# EN-C200_RA0_USB.net
KiCad netlist of a schematic drawn in Altium Designer
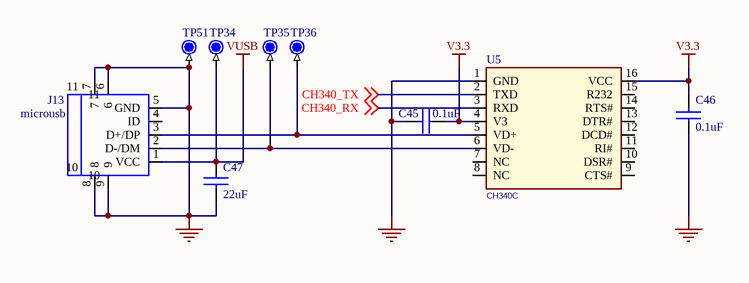
[diagram p0: EN-C200_RA0_USB.SchDoc]

(export (version "E")
  (design (tool "Eeschema 10.0.6"))
  (components
    (comp (ref "C45") (value "0.1uF") (footprint "SC0603") (libsource (lib "EN-C200_RA0") (part "CAP NP")))
    (comp (ref "C46") (value "0.1uF") (footprint "SC0603") (libsource (lib "EN-C200_RA0") (part "CAP NP")))
    (comp (ref "C47") (value "22uF") (footprint "SC0805") (libsource (lib "EN-C200_RA0") (part "CAP NP")))
    (comp (ref "J13")
      (value "microusb")
      (footprint "MICROUSB_D")
      (libsource (lib "EN-C200_RA0") (part "microusb"))
    )
    (comp (ref "TP34") (value "NC") (footprint "TP32-SMD") (libsource (lib "EN-C200_RA0") (part "TP")))
    (comp (ref "TP35") (value "NC") (footprint "TP32-SMD") (libsource (lib "EN-C200_RA0") (part "TP")))
    (comp (ref "TP36") (value "NC") (footprint "TP32-SMD") (libsource (lib "EN-C200_RA0") (part "TP")))
    (comp (ref "TP51") (value "NC") (footprint "TP32-SMD") (libsource (lib "EN-C200_RA0") (part "TP")))
    (comp (ref "U5")
      (value "CH340C")
      (footprint "SOP16-50-150A")
      (libsource (lib "EN-C200_RA0") (part "CH340C_0"))
    )
  )
  (nets
    (net (code "1") (name "CH340_RX") (class "Default")
      (node (ref "U5") (pin "3") (pinfunction "RXD_3") (pintype "passive"))
    )
    (net (code "2") (name "CH340_TX") (class "Default")
      (node (ref "U5") (pin "2") (pinfunction "TXD_2") (pintype "passive"))
    )
    (net (code "3") (name "GND") (class "Default")
      (node (ref "C45") (pin "2") (pinfunction "2_2") (pintype "passive"))
      (node (ref "C46") (pin "1") (pinfunction "1_1") (pintype "passive"))
      (node (ref "C47") (pin "2") (pinfunction "2_2") (pintype "passive"))
      (node (ref "J13") (pin "5") (pinfunction "GND_5") (pintype "passive"))
      (node (ref "J13") (pin "6") (pinfunction "6_6") (pintype "passive"))
      (node (ref "J13") (pin "7") (pinfunction "7_7") (pintype "passive"))
      (node (ref "J13") (pin "8") (pinfunction "8_8") (pintype "passive"))
      (node (ref "J13") (pin "9") (pinfunction "9_9") (pintype "passive"))
      (node (ref "TP51") (pin "1") (pinfunction "1_1") (pintype "input"))
      (node (ref "U5") (pin "1") (pinfunction "GND_1") (pintype "power_in"))
    )
    (net (code "4") (name "Net-(J13-D+{slash}DP)") (class "Default")
      (node (ref "J13") (pin "3") (pinfunction "D+/DP_3") (pintype "passive"))
      (node (ref "TP36") (pin "1") (pinfunction "1_1") (pintype "input"))
      (node (ref "U5") (pin "5") (pinfunction "VD+_5") (pintype "passive"))
    )
    (net (code "5") (name "Net-(J13-D-{slash}DM)") (class "Default")
      (node (ref "J13") (pin "2") (pinfunction "D-/DM_2") (pintype "passive"))
      (node (ref "TP35") (pin "1") (pinfunction "1_1") (pintype "input"))
      (node (ref "U5") (pin "6") (pinfunction "VD-_6") (pintype "passive"))
    )
    (net (code "6") (name "V3.3") (class "Default")
      (node (ref "C45") (pin "1") (pinfunction "1_1") (pintype "passive"))
      (node (ref "C46") (pin "2") (pinfunction "2_2") (pintype "passive"))
      (node (ref "U5") (pin "16") (pinfunction "VCC_16") (pintype "power_in"))
      (node (ref "U5") (pin "4") (pinfunction "V3_4") (pintype "passive"))
    )
    (net (code "7") (name "VUSB") (class "Default")
      (node (ref "C47") (pin "1") (pinfunction "1_1") (pintype "passive"))
      (node (ref "J13") (pin "1") (pinfunction "VCC_1") (pintype "passive"))
      (node (ref "TP34") (pin "1") (pinfunction "1_1") (pintype "input"))
    )
    (net (code "8") (name "unconnected-(J13-ID-Pad4)") (class "Default")
      (node (ref "J13") (pin "4") (pinfunction "ID_4") (pintype "passive"))
    )
    (net (code "9") (name "unconnected-(J13-Pad10)") (class "Default")
      (node (ref "J13") (pin "10") (pinfunction "10_10") (pintype "passive"))
    )
    (net (code "10") (name "unconnected-(J13-Pad11)") (class "Default")
      (node (ref "J13") (pin "11") (pinfunction "11_11") (pintype "passive"))
    )
    (net (code "11") (name "unconnected-(U5-CTS#-Pad9)") (class "Default")
      (node (ref "U5") (pin "9") (pinfunction "CTS#_9") (pintype "passive"))
    )
    (net (code "12") (name "unconnected-(U5-DCD#-Pad12)") (class "Default")
      (node (ref "U5") (pin "12") (pinfunction "DCD#_12") (pintype "passive"))
    )
    (net (code "13") (name "unconnected-(U5-DSR#-Pad10)") (class "Default")
      (node (ref "U5") (pin "10") (pinfunction "DSR#_10") (pintype "passive"))
    )
    (net (code "14") (name "unconnected-(U5-DTR#-Pad13)") (class "Default")
      (node (ref "U5") (pin "13") (pinfunction "DTR#_13") (pintype "passive"))
    )
    (net (code "15") (name "unconnected-(U5-NC-Pad7)") (class "Default")
      (node (ref "U5") (pin "7") (pinfunction "NC_7") (pintype "passive"))
    )
    (net (code "16") (name "unconnected-(U5-NC-Pad8)") (class "Default")
      (node (ref "U5") (pin "8") (pinfunction "NC_8") (pintype "passive"))
    )
    (net (code "17") (name "unconnected-(U5-R232-Pad15)") (class "Default")
      (node (ref "U5") (pin "15") (pinfunction "R232_15") (pintype "passive"))
    )
    (net (code "18") (name "unconnected-(U5-RI#-Pad11)") (class "Default")
      (node (ref "U5") (pin "11") (pinfunction "RI#_11") (pintype "passive"))
    )
    (net (code "19") (name "unconnected-(U5-RTS#-Pad14)") (class "Default")
      (node (ref "U5") (pin "14") (pinfunction "RTS#_14") (pintype "passive"))
    )
  )
)
